# dimmerPower2.net
KiCad netlist of a schematic drawn in EAGLE
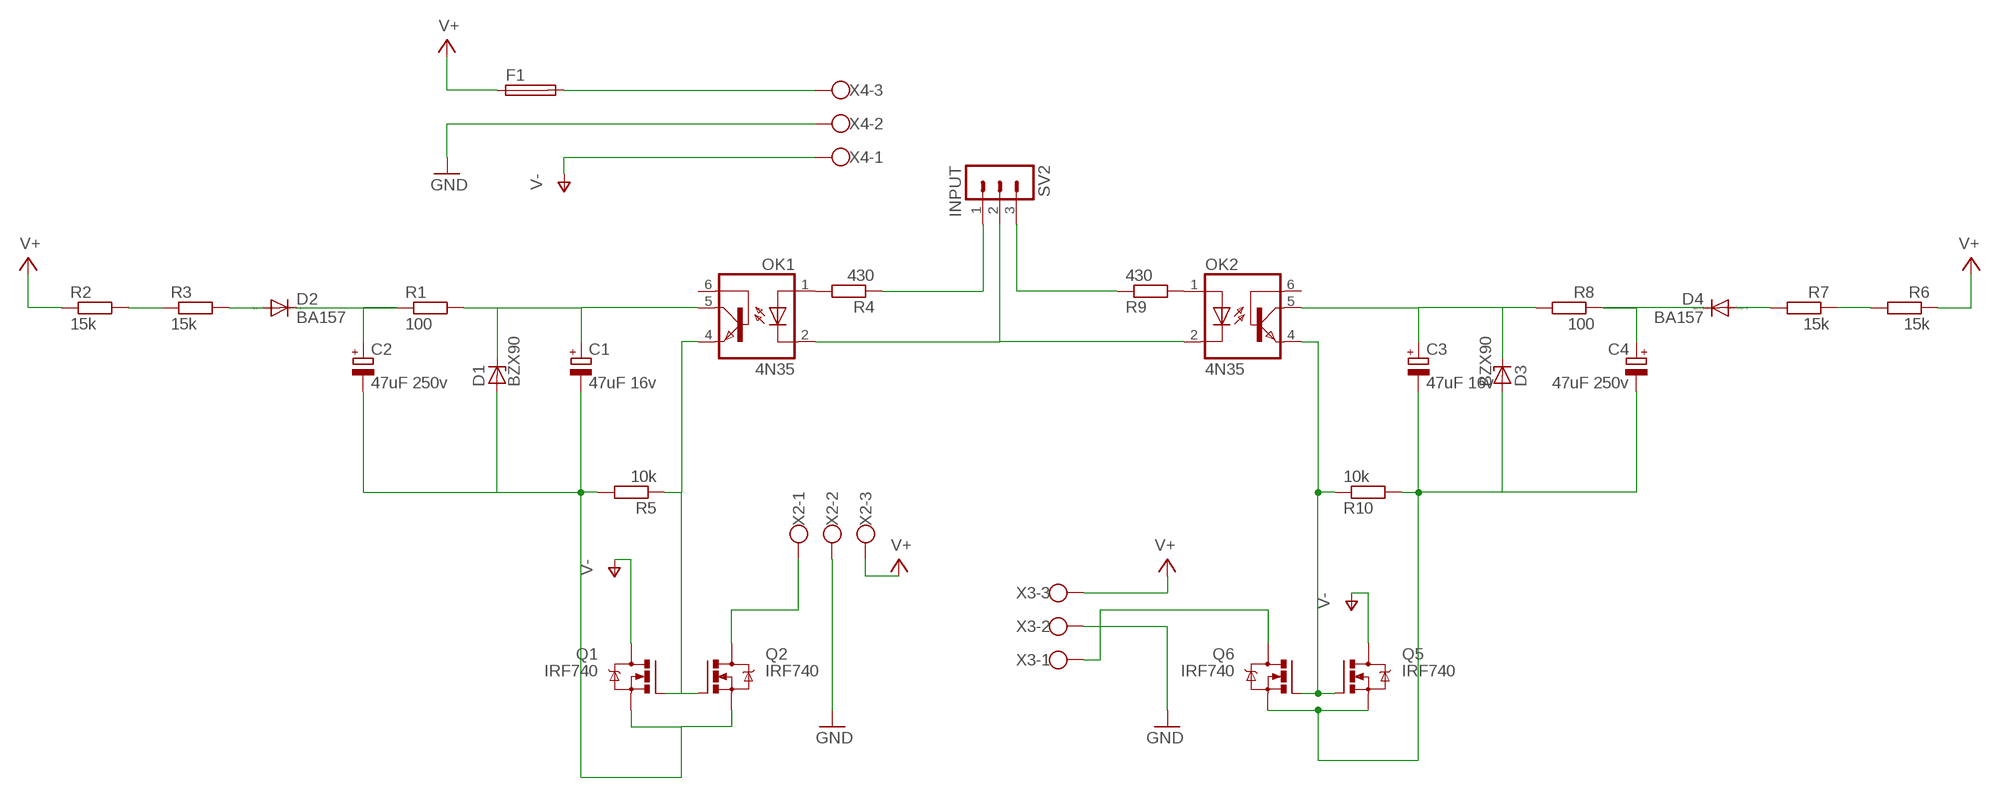
[diagram p0: schematic, sheet 1]

(export (version "E")
  (design (tool "Eeschema 10.0.6"))
  (components
    (comp (ref "C1")
      (value "47uF 16v")
      (footprint "eagle-import:E2,5-6")
      (libsource (lib "eagle-import") (part "CPOL-EUE2.5-6"))
    )
    (comp (ref "C2")
      (value "47uF 250v")
      (footprint "eagle-import:E5-13")
      (libsource (lib "eagle-import") (part "CPOL-EUE5-13"))
    )
    (comp (ref "C3")
      (value "47uF 16v")
      (footprint "eagle-import:E2,5-6")
      (libsource (lib "eagle-import") (part "CPOL-EUE2.5-6"))
    )
    (comp (ref "C4")
      (value "47uF 250v")
      (footprint "eagle-import:E5-13")
      (libsource (lib "eagle-import") (part "CPOL-EUE5-13"))
    )
    (comp (ref "D1")
      (value "BZX90")
      (footprint "eagle-import:DO34Z7")
      (libsource (lib "eagle-import") (part "BZX90"))
    )
    (comp (ref "D2")
      (value "BA157")
      (footprint "eagle-import:P1-10")
      (libsource (lib "eagle-import") (part "BA157"))
    )
    (comp (ref "D3")
      (value "BZX90")
      (footprint "eagle-import:DO34Z7")
      (libsource (lib "eagle-import") (part "BZX90"))
    )
    (comp (ref "D4")
      (value "BA157")
      (footprint "eagle-import:P1-10")
      (libsource (lib "eagle-import") (part "BA157"))
    )
    (comp (ref "F1")
      (value "SH22,5")
      (footprint "eagle-import:SH22,5")
      (fields (field (name "MF") "SCHURTER") (field (name "MPN") "0031.8201"))
      (libsource (lib "eagle-import") (part "SH22,5"))
    )
    (comp (ref "OK1")
      (value "4N35")
      (footprint "eagle-import:DIL06")
      (fields (field (name "MF") "FAIRCHILD SEMICONDUCTOR"))
      (libsource (lib "eagle-import") (part "4N35"))
    )
    (comp (ref "OK2")
      (value "4N35")
      (footprint "eagle-import:DIL06")
      (fields (field (name "MF") "FAIRCHILD SEMICONDUCTOR"))
      (libsource (lib "eagle-import") (part "4N35"))
    )
    (comp (ref "Q1")
      (value "IRF740")
      (footprint "eagle-import:TO220BV")
      (libsource (lib "eagle-import") (part "IRF740"))
    )
    (comp (ref "Q2")
      (value "IRF740")
      (footprint "eagle-import:TO220BV")
      (libsource (lib "eagle-import") (part "IRF740"))
    )
    (comp (ref "Q5")
      (value "IRF740")
      (footprint "eagle-import:TO220BV")
      (libsource (lib "eagle-import") (part "IRF740"))
    )
    (comp (ref "Q6")
      (value "IRF740")
      (footprint "eagle-import:TO220BV")
      (libsource (lib "eagle-import") (part "IRF740"))
    )
    (comp (ref "R1")
      (value "100")
      (footprint "eagle-import:0204_7")
      (libsource (lib "eagle-import") (part "R-EU_0204/7"))
    )
    (comp (ref "R2")
      (value "15k")
      (footprint "eagle-import:P0613_15")
      (libsource (lib "eagle-import") (part "R-EU_0613/15"))
    )
    (comp (ref "R3")
      (value "15k")
      (footprint "eagle-import:P0613_15")
      (libsource (lib "eagle-import") (part "R-EU_0613/15"))
    )
    (comp (ref "R4")
      (value "430")
      (footprint "eagle-import:0204_7")
      (libsource (lib "eagle-import") (part "R-EU_0204/7"))
    )
    (comp (ref "R5")
      (value "10k")
      (footprint "eagle-import:0204_7")
      (libsource (lib "eagle-import") (part "R-EU_0204/7"))
    )
    (comp (ref "R6")
      (value "15k")
      (footprint "eagle-import:P0613_15")
      (libsource (lib "eagle-import") (part "R-EU_0613/15"))
    )
    (comp (ref "R7")
      (value "15k")
      (footprint "eagle-import:P0613_15")
      (libsource (lib "eagle-import") (part "R-EU_0613/15"))
    )
    (comp (ref "R8")
      (value "100")
      (footprint "eagle-import:0204_7")
      (libsource (lib "eagle-import") (part "R-EU_0204/7"))
    )
    (comp (ref "R9")
      (value "430")
      (footprint "eagle-import:0204_7")
      (libsource (lib "eagle-import") (part "R-EU_0204/7"))
    )
    (comp (ref "R10")
      (value "10k")
      (footprint "eagle-import:0204_7")
      (libsource (lib "eagle-import") (part "R-EU_0204/7"))
    )
    (comp (ref "SV2")
      (value "INPUT")
      (footprint "eagle-import:MA03-1")
      (libsource (lib "eagle-import") (part "MA03-1"))
    )
    (comp (ref "X2")
      (value "W237-103")
      (footprint "eagle-import:W237-103")
      (fields (field (name "MPN") "237-103"))
      (libsource (lib "eagle-import") (part "W237-103"))
    )
    (comp (ref "X3")
      (value "W237-103")
      (footprint "eagle-import:W237-103")
      (fields (field (name "MPN") "237-103"))
      (libsource (lib "eagle-import") (part "W237-103"))
    )
    (comp (ref "X4")
      (value "W237-103")
      (footprint "eagle-import:W237-103")
      (fields (field (name "MPN") "237-103"))
      (libsource (lib "eagle-import") (part "W237-103"))
    )
  )
  (nets
    (net (code "1") (name "GND") (class "Default")
      (node (ref "X2") (pin "2") (pinfunction "KL_2") (pintype "passive"))
      (node (ref "X3") (pin "2") (pinfunction "KL_2") (pintype "passive"))
      (node (ref "X4") (pin "2") (pinfunction "KL_2") (pintype "passive"))
    )
    (net (code "2") (name "Net-(C1-Pad-)") (class "Default")
      (node (ref "C1") (pin "-") (pinfunction "-_-") (pintype "passive"))
      (node (ref "C2") (pin "-") (pinfunction "-_-") (pintype "passive"))
      (node (ref "D1") (pin "A") (pinfunction "A_A") (pintype "passive"))
      (node (ref "Q1") (pin "S") (pinfunction "S_S") (pintype "passive"))
      (node (ref "Q2") (pin "S") (pinfunction "S_S") (pintype "passive"))
      (node (ref "R5") (pin "2") (pinfunction "2_2") (pintype "passive"))
    )
    (net (code "3") (name "Net-(C2-Pad+)") (class "Default")
      (node (ref "C2") (pin "+") (pinfunction "+_+") (pintype "passive"))
      (node (ref "D2") (pin "C") (pinfunction "C_C") (pintype "passive"))
      (node (ref "R1") (pin "1") (pinfunction "1_1") (pintype "passive"))
    )
    (net (code "4") (name "Net-(C3-Pad-)") (class "Default")
      (node (ref "C3") (pin "-") (pinfunction "-_-") (pintype "passive"))
      (node (ref "C4") (pin "-") (pinfunction "-_-") (pintype "passive"))
      (node (ref "D3") (pin "A") (pinfunction "A_A") (pintype "passive"))
      (node (ref "Q5") (pin "S") (pinfunction "S_S") (pintype "passive"))
      (node (ref "Q6") (pin "S") (pinfunction "S_S") (pintype "passive"))
      (node (ref "R10") (pin "2") (pinfunction "2_2") (pintype "passive"))
    )
    (net (code "5") (name "Net-(C4-Pad+)") (class "Default")
      (node (ref "C4") (pin "+") (pinfunction "+_+") (pintype "passive"))
      (node (ref "D4") (pin "C") (pinfunction "C_C") (pintype "passive"))
      (node (ref "R8") (pin "1") (pinfunction "1_1") (pintype "passive"))
    )
    (net (code "6") (name "Net-(D2-PadA)") (class "Default")
      (node (ref "D2") (pin "A") (pinfunction "A_A") (pintype "passive"))
      (node (ref "R3") (pin "2") (pinfunction "2_2") (pintype "passive"))
    )
    (net (code "7") (name "Net-(D4-PadA)") (class "Default")
      (node (ref "D4") (pin "A") (pinfunction "A_A") (pintype "passive"))
      (node (ref "R7") (pin "2") (pinfunction "2_2") (pintype "passive"))
    )
    (net (code "8") (name "Net-(OK1-A)") (class "Default")
      (node (ref "OK1") (pin "1") (pinfunction "A_1") (pintype "passive"))
      (node (ref "R4") (pin "2") (pinfunction "2_2") (pintype "passive"))
    )
    (net (code "9") (name "Net-(OK1-C)") (class "Default")
      (node (ref "OK1") (pin "2") (pinfunction "C_2") (pintype "passive"))
      (node (ref "OK2") (pin "2") (pinfunction "C_2") (pintype "passive"))
      (node (ref "SV2") (pin "2") (pinfunction "2_2") (pintype "passive"))
    )
    (net (code "10") (name "Net-(OK1-COL)") (class "Default")
      (node (ref "C1") (pin "+") (pinfunction "+_+") (pintype "passive"))
      (node (ref "D1") (pin "C") (pinfunction "C_C") (pintype "passive"))
      (node (ref "OK1") (pin "5") (pinfunction "COL_5") (pintype "passive"))
      (node (ref "R1") (pin "2") (pinfunction "2_2") (pintype "passive"))
    )
    (net (code "11") (name "Net-(OK1-EMI)") (class "Default")
      (node (ref "OK1") (pin "4") (pinfunction "EMI_4") (pintype "passive"))
      (node (ref "Q1") (pin "G") (pinfunction "G_G") (pintype "passive"))
      (node (ref "Q2") (pin "G") (pinfunction "G_G") (pintype "passive"))
      (node (ref "R5") (pin "1") (pinfunction "1_1") (pintype "passive"))
    )
    (net (code "12") (name "Net-(OK2-A)") (class "Default")
      (node (ref "OK2") (pin "1") (pinfunction "A_1") (pintype "passive"))
      (node (ref "R9") (pin "2") (pinfunction "2_2") (pintype "passive"))
    )
    (net (code "13") (name "Net-(OK2-COL)") (class "Default")
      (node (ref "C3") (pin "+") (pinfunction "+_+") (pintype "passive"))
      (node (ref "D3") (pin "C") (pinfunction "C_C") (pintype "passive"))
      (node (ref "OK2") (pin "5") (pinfunction "COL_5") (pintype "passive"))
      (node (ref "R8") (pin "2") (pinfunction "2_2") (pintype "passive"))
    )
    (net (code "14") (name "Net-(OK2-EMI)") (class "Default")
      (node (ref "OK2") (pin "4") (pinfunction "EMI_4") (pintype "passive"))
      (node (ref "Q5") (pin "G") (pinfunction "G_G") (pintype "passive"))
      (node (ref "Q6") (pin "G") (pinfunction "G_G") (pintype "passive"))
      (node (ref "R10") (pin "1") (pinfunction "1_1") (pintype "passive"))
    )
    (net (code "15") (name "Net-(R2-Pad2)") (class "Default")
      (node (ref "R2") (pin "2") (pinfunction "2_2") (pintype "passive"))
      (node (ref "R3") (pin "1") (pinfunction "1_1") (pintype "passive"))
    )
    (net (code "16") (name "Net-(R4-Pad1)") (class "Default")
      (node (ref "R4") (pin "1") (pinfunction "1_1") (pintype "passive"))
      (node (ref "SV2") (pin "1") (pinfunction "1_1") (pintype "passive"))
    )
    (net (code "17") (name "Net-(R6-Pad2)") (class "Default")
      (node (ref "R6") (pin "2") (pinfunction "2_2") (pintype "passive"))
      (node (ref "R7") (pin "1") (pinfunction "1_1") (pintype "passive"))
    )
    (net (code "18") (name "Net-(R9-Pad1)") (class "Default")
      (node (ref "R9") (pin "1") (pinfunction "1_1") (pintype "passive"))
      (node (ref "SV2") (pin "3") (pinfunction "3_3") (pintype "passive"))
    )
    (net (code "19") (name "Net-(X2A-KL)") (class "Default")
      (node (ref "Q2") (pin "D") (pinfunction "D_D") (pintype "passive"))
      (node (ref "X2") (pin "1") (pinfunction "KL_1") (pintype "passive"))
    )
    (net (code "20") (name "Net-(X3A-KL)") (class "Default")
      (node (ref "Q6") (pin "D") (pinfunction "D_D") (pintype "passive"))
      (node (ref "X3") (pin "1") (pinfunction "KL_1") (pintype "passive"))
    )
    (net (code "21") (name "Net-(X4C-KL)") (class "Default")
      (node (ref "F1") (pin "2") (pinfunction "2_2") (pintype "passive"))
      (node (ref "X4") (pin "3") (pinfunction "KL_3") (pintype "passive"))
    )
    (net (code "22") (name "V+") (class "Default")
      (node (ref "F1") (pin "1") (pinfunction "1_1") (pintype "passive"))
      (node (ref "R2") (pin "1") (pinfunction "1_1") (pintype "passive"))
      (node (ref "R6") (pin "1") (pinfunction "1_1") (pintype "passive"))
      (node (ref "X2") (pin "3") (pinfunction "KL_3") (pintype "passive"))
      (node (ref "X3") (pin "3") (pinfunction "KL_3") (pintype "passive"))
    )
    (net (code "23") (name "V-") (class "Default")
      (node (ref "Q1") (pin "D") (pinfunction "D_D") (pintype "passive"))
      (node (ref "Q5") (pin "D") (pinfunction "D_D") (pintype "passive"))
      (node (ref "X4") (pin "1") (pinfunction "KL_1") (pintype "passive"))
    )
    (net (code "24") (name "unconnected-(OK1-BAS-Pad6)") (class "Default")
      (node (ref "OK1") (pin "6") (pinfunction "BAS_6") (pintype "passive"))
    )
    (net (code "25") (name "unconnected-(OK2-BAS-Pad6)") (class "Default")
      (node (ref "OK2") (pin "6") (pinfunction "BAS_6") (pintype "passive"))
    )
  )
)
